# 5ButtonSwitch_ItsyBitsyM0_Rev1_1.net
KiCad netlist of a schematic drawn in EAGLE
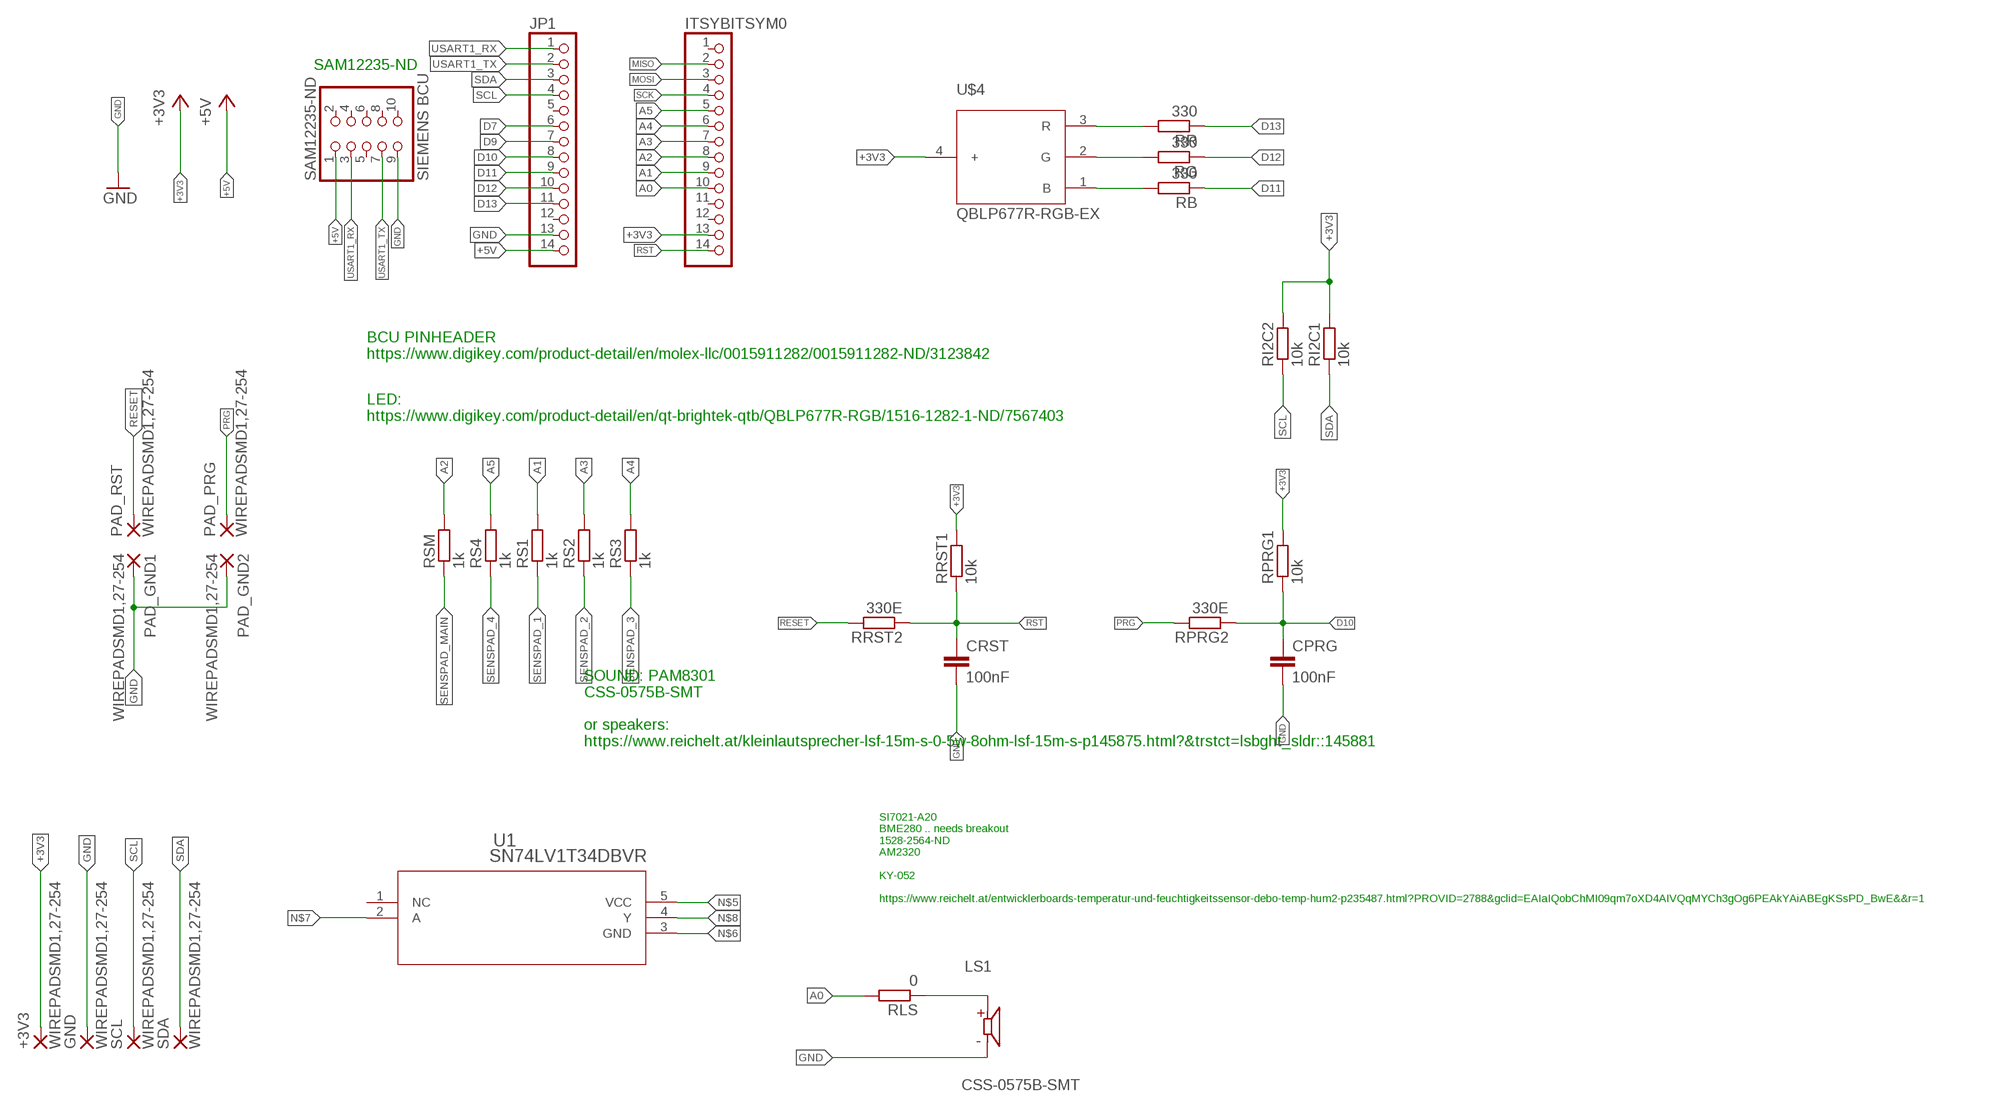
[diagram p0: schematic, sheet 1]

(export (version "E")
  (design (tool "Eeschema 10.0.6"))
  (components
    (comp (ref "+3V3")
      (value "WIREPADSMD1,27-254")
      (footprint "eagle-import:SMD1,27-2,54")
      (libsource (lib "eagle-import") (part "WIREPADSMD1,27-254"))
    )
    (comp (ref "CPRG")
      (value "100nF")
      (footprint "eagle-import:C1206")
      (libsource (lib "eagle-import") (part "C-EUC1206"))
    )
    (comp (ref "CRST")
      (value "100nF")
      (footprint "eagle-import:C1206")
      (libsource (lib "eagle-import") (part "C-EUC1206"))
    )
    (comp (ref "GND")
      (value "WIREPADSMD1,27-254")
      (footprint "eagle-import:SMD1,27-2,54")
      (libsource (lib "eagle-import") (part "WIREPADSMD1,27-254"))
    )
    (comp (ref "ITSYBITSYM0")
      (value "PINHD-1X141X14_SMT")
      (footprint "eagle-import:1X14_SMT")
      (libsource (lib "eagle-import") (part "PINHD-1X141X14_SMT"))
    )
    (comp (ref "JP1")
      (value "PINHD-1X141X14_SMT")
      (footprint "eagle-import:1X14_SMT")
      (libsource (lib "eagle-import") (part "PINHD-1X141X14_SMT"))
    )
    (comp (ref "LS1")
      (value "CSS-0575B-SMT")
      (footprint "eagle-import:CUI_CSS-0575B-SMT")
      (fields
        (field (name "DIGI-KEY_PART_NUMBER") "102-2202-1-ND")
        (field (name "MF") "CUI Inc.")
        (field (name "MP") "CSS-0575B-SMT-TR")
      )
      (libsource (lib "eagle-import") (part "CSS-0575B-SMT"))
    )
    (comp (ref "PAD_GND1")
      (value "WIREPADSMD1,27-254")
      (footprint "eagle-import:SMD1,27-2,54")
      (libsource (lib "eagle-import") (part "WIREPADSMD1,27-254"))
    )
    (comp (ref "PAD_GND2")
      (value "WIREPADSMD1,27-254")
      (footprint "eagle-import:SMD1,27-2,54")
      (libsource (lib "eagle-import") (part "WIREPADSMD1,27-254"))
    )
    (comp (ref "PAD_PRG")
      (value "WIREPADSMD1,27-254")
      (footprint "eagle-import:SMD1,27-2,54")
      (libsource (lib "eagle-import") (part "WIREPADSMD1,27-254"))
    )
    (comp (ref "PAD_RST")
      (value "WIREPADSMD1,27-254")
      (footprint "eagle-import:SMD1,27-2,54")
      (libsource (lib "eagle-import") (part "WIREPADSMD1,27-254"))
    )
    (comp (ref "RB")
      (value "330")
      (footprint "eagle-import:R1206")
      (libsource (lib "eagle-import") (part "R-EU_R1206"))
    )
    (comp (ref "RG")
      (value "330")
      (footprint "eagle-import:R1206")
      (libsource (lib "eagle-import") (part "R-EU_R1206"))
    )
    (comp (ref "RI2C1")
      (value "10k")
      (footprint "eagle-import:R1206")
      (libsource (lib "eagle-import") (part "R-EU_R1206"))
    )
    (comp (ref "RI2C2")
      (value "10k")
      (footprint "eagle-import:R1206")
      (libsource (lib "eagle-import") (part "R-EU_R1206"))
    )
    (comp (ref "RLS")
      (value "0")
      (footprint "eagle-import:R1206")
      (libsource (lib "eagle-import") (part "R-EU_R1206"))
    )
    (comp (ref "RPRG1")
      (value "10k")
      (footprint "eagle-import:R1206")
      (libsource (lib "eagle-import") (part "R-EU_R1206"))
    )
    (comp (ref "RPRG2")
      (value "330E")
      (footprint "eagle-import:R1206")
      (libsource (lib "eagle-import") (part "R-EU_R1206"))
    )
    (comp (ref "RR")
      (value "330")
      (footprint "eagle-import:R1206")
      (libsource (lib "eagle-import") (part "R-EU_R1206"))
    )
    (comp (ref "RRST1")
      (value "10k")
      (footprint "eagle-import:R1206")
      (libsource (lib "eagle-import") (part "R-EU_R1206"))
    )
    (comp (ref "RRST2")
      (value "330E")
      (footprint "eagle-import:R1206")
      (libsource (lib "eagle-import") (part "R-EU_R1206"))
    )
    (comp (ref "RS1")
      (value "1k")
      (footprint "eagle-import:R1206")
      (libsource (lib "eagle-import") (part "R-EU_R1206"))
    )
    (comp (ref "RS2")
      (value "1k")
      (footprint "eagle-import:R1206")
      (libsource (lib "eagle-import") (part "R-EU_R1206"))
    )
    (comp (ref "RS3")
      (value "1k")
      (footprint "eagle-import:R1206")
      (libsource (lib "eagle-import") (part "R-EU_R1206"))
    )
    (comp (ref "RS4")
      (value "1k")
      (footprint "eagle-import:R1206")
      (libsource (lib "eagle-import") (part "R-EU_R1206"))
    )
    (comp (ref "RSM")
      (value "1k")
      (footprint "eagle-import:R1206")
      (libsource (lib "eagle-import") (part "R-EU_R1206"))
    )
    (comp (ref "SAM12235-ND")
      (value "SIEMENS BCU")
      (footprint "eagle-import:2X05SMD")
      (libsource (lib "eagle-import") (part "PINHD-2X5_2.54-SMD"))
    )
    (comp (ref "SCL")
      (value "WIREPADSMD1,27-254")
      (footprint "eagle-import:SMD1,27-2,54")
      (libsource (lib "eagle-import") (part "WIREPADSMD1,27-254"))
    )
    (comp (ref "SDA")
      (value "WIREPADSMD1,27-254")
      (footprint "eagle-import:SMD1,27-2,54")
      (libsource (lib "eagle-import") (part "WIREPADSMD1,27-254"))
    )
    (comp (ref "U$4")
      (value "QBLP677R-RGB-EX")
      (footprint "eagle-import:PLCC4R_EX")
      (libsource (lib "eagle-import") (part "QBLP677R-RGB-EX"))
    )
    (comp (ref "U1")
      (value "SN74LV1T34DBVR")
      (footprint "eagle-import:DBV5")
      (libsource (lib "eagle-import") (part "SN74LV1T34DBVR"))
    )
  )
  (nets
    (net (code "1") (name "+3V3") (class "Default")
      (node (ref "+3V3") (pin "1") (pinfunction "P_1") (pintype "passive"))
      (node (ref "ITSYBITSYM0") (pin "13") (pinfunction "13_13") (pintype "passive"))
      (node (ref "RI2C1") (pin "2") (pinfunction "2_2") (pintype "passive"))
      (node (ref "RI2C2") (pin "2") (pinfunction "2_2") (pintype "passive"))
      (node (ref "RPRG1") (pin "2") (pinfunction "2_2") (pintype "passive"))
      (node (ref "RRST1") (pin "2") (pinfunction "2_2") (pintype "passive"))
      (node (ref "U$4") (pin "4") (pinfunction "+_4") (pintype "power_in"))
    )
    (net (code "2") (name "+5V") (class "Default")
      (node (ref "JP1") (pin "14") (pinfunction "14_14") (pintype "passive"))
      (node (ref "SAM12235-ND") (pin "1") (pinfunction "1_1") (pintype "passive"))
    )
    (net (code "3") (name "A0") (class "Default")
      (node (ref "ITSYBITSYM0") (pin "10") (pinfunction "10_10") (pintype "passive"))
      (node (ref "RLS") (pin "2") (pinfunction "2_2") (pintype "passive"))
    )
    (net (code "4") (name "A1") (class "Default")
      (node (ref "ITSYBITSYM0") (pin "9") (pinfunction "9_9") (pintype "passive"))
      (node (ref "RS1") (pin "2") (pinfunction "2_2") (pintype "passive"))
    )
    (net (code "5") (name "A2") (class "Default")
      (node (ref "ITSYBITSYM0") (pin "8") (pinfunction "8_8") (pintype "passive"))
      (node (ref "RSM") (pin "2") (pinfunction "2_2") (pintype "passive"))
    )
    (net (code "6") (name "A3") (class "Default")
      (node (ref "ITSYBITSYM0") (pin "7") (pinfunction "7_7") (pintype "passive"))
      (node (ref "RS2") (pin "2") (pinfunction "2_2") (pintype "passive"))
    )
    (net (code "7") (name "A4") (class "Default")
      (node (ref "ITSYBITSYM0") (pin "6") (pinfunction "6_6") (pintype "passive"))
      (node (ref "RS3") (pin "2") (pinfunction "2_2") (pintype "passive"))
    )
    (net (code "8") (name "A5") (class "Default")
      (node (ref "ITSYBITSYM0") (pin "5") (pinfunction "5_5") (pintype "passive"))
      (node (ref "RS4") (pin "2") (pinfunction "2_2") (pintype "passive"))
    )
    (net (code "9") (name "D7") (class "Default")
      (node (ref "JP1") (pin "6") (pinfunction "6_6") (pintype "passive"))
    )
    (net (code "10") (name "D9") (class "Default")
      (node (ref "JP1") (pin "7") (pinfunction "7_7") (pintype "passive"))
    )
    (net (code "11") (name "D10") (class "Default")
      (node (ref "CPRG") (pin "1") (pinfunction "1_1") (pintype "passive"))
      (node (ref "JP1") (pin "8") (pinfunction "8_8") (pintype "passive"))
      (node (ref "RPRG1") (pin "1") (pinfunction "1_1") (pintype "passive"))
      (node (ref "RPRG2") (pin "1") (pinfunction "1_1") (pintype "passive"))
    )
    (net (code "12") (name "D11") (class "Default")
      (node (ref "JP1") (pin "9") (pinfunction "9_9") (pintype "passive"))
      (node (ref "RB") (pin "1") (pinfunction "1_1") (pintype "passive"))
    )
    (net (code "13") (name "D12") (class "Default")
      (node (ref "JP1") (pin "10") (pinfunction "10_10") (pintype "passive"))
      (node (ref "RG") (pin "1") (pinfunction "1_1") (pintype "passive"))
    )
    (net (code "14") (name "D13") (class "Default")
      (node (ref "JP1") (pin "11") (pinfunction "11_11") (pintype "passive"))
      (node (ref "RR") (pin "1") (pinfunction "1_1") (pintype "passive"))
    )
    (net (code "15") (name "GND") (class "Default")
      (node (ref "CPRG") (pin "2") (pinfunction "2_2") (pintype "passive"))
      (node (ref "CRST") (pin "2") (pinfunction "2_2") (pintype "passive"))
      (node (ref "GND") (pin "1") (pinfunction "P_1") (pintype "passive"))
      (node (ref "JP1") (pin "13") (pinfunction "13_13") (pintype "passive"))
      (node (ref "LS1") (pin "2") (pinfunction "N_2") (pintype "passive"))
      (node (ref "PAD_GND1") (pin "1") (pinfunction "P_1") (pintype "passive"))
      (node (ref "PAD_GND2") (pin "1") (pinfunction "P_1") (pintype "passive"))
      (node (ref "SAM12235-ND") (pin "9") (pinfunction "9_9") (pintype "passive"))
    )
    (net (code "16") (name "MISO") (class "Default")
      (node (ref "ITSYBITSYM0") (pin "2") (pinfunction "2_2") (pintype "passive"))
    )
    (net (code "17") (name "MOSI") (class "Default")
      (node (ref "ITSYBITSYM0") (pin "3") (pinfunction "3_3") (pintype "passive"))
    )
    (net (code "18") (name "N$5") (class "Default")
      (node (ref "U1") (pin "5") (pinfunction "VCC_5") (pintype "power_in"))
    )
    (net (code "19") (name "N$6") (class "Default")
      (node (ref "U1") (pin "3") (pinfunction "GND_3") (pintype "power_in"))
    )
    (net (code "20") (name "N$7") (class "Default")
      (node (ref "U1") (pin "2") (pinfunction "A_2") (pintype "input"))
    )
    (net (code "21") (name "N$8") (class "Default")
      (node (ref "U1") (pin "4") (pinfunction "Y_4") (pintype "output"))
    )
    (net (code "22") (name "Net-(LS1-P)") (class "Default")
      (node (ref "LS1") (pin "1") (pinfunction "P_1") (pintype "passive"))
      (node (ref "RLS") (pin "1") (pinfunction "1_1") (pintype "passive"))
    )
    (net (code "23") (name "Net-(U$4-B)") (class "Default")
      (node (ref "RB") (pin "2") (pinfunction "2_2") (pintype "passive"))
      (node (ref "U$4") (pin "1") (pinfunction "B_1") (pintype "output"))
    )
    (net (code "24") (name "Net-(U$4-G)") (class "Default")
      (node (ref "RG") (pin "2") (pinfunction "2_2") (pintype "passive"))
      (node (ref "U$4") (pin "2") (pinfunction "G_2") (pintype "output"))
    )
    (net (code "25") (name "Net-(U$4-R)") (class "Default")
      (node (ref "RR") (pin "2") (pinfunction "2_2") (pintype "passive"))
      (node (ref "U$4") (pin "3") (pinfunction "R_3") (pintype "output"))
    )
    (net (code "26") (name "PRG") (class "Default")
      (node (ref "PAD_PRG") (pin "1") (pinfunction "P_1") (pintype "passive"))
      (node (ref "RPRG2") (pin "2") (pinfunction "2_2") (pintype "passive"))
    )
    (net (code "27") (name "RESET") (class "Default")
      (node (ref "PAD_RST") (pin "1") (pinfunction "P_1") (pintype "passive"))
      (node (ref "RRST2") (pin "2") (pinfunction "2_2") (pintype "passive"))
    )
    (net (code "28") (name "RST") (class "Default")
      (node (ref "CRST") (pin "1") (pinfunction "1_1") (pintype "passive"))
      (node (ref "ITSYBITSYM0") (pin "14") (pinfunction "14_14") (pintype "passive"))
      (node (ref "RRST1") (pin "1") (pinfunction "1_1") (pintype "passive"))
      (node (ref "RRST2") (pin "1") (pinfunction "1_1") (pintype "passive"))
    )
    (net (code "29") (name "SCK") (class "Default")
      (node (ref "ITSYBITSYM0") (pin "4") (pinfunction "4_4") (pintype "passive"))
    )
    (net (code "30") (name "SCL") (class "Default")
      (node (ref "JP1") (pin "4") (pinfunction "4_4") (pintype "passive"))
      (node (ref "RI2C2") (pin "1") (pinfunction "1_1") (pintype "passive"))
      (node (ref "SCL") (pin "1") (pinfunction "P_1") (pintype "passive"))
    )
    (net (code "31") (name "SDA") (class "Default")
      (node (ref "JP1") (pin "3") (pinfunction "3_3") (pintype "passive"))
      (node (ref "RI2C1") (pin "1") (pinfunction "1_1") (pintype "passive"))
      (node (ref "SDA") (pin "1") (pinfunction "P_1") (pintype "passive"))
    )
    (net (code "32") (name "SENSPAD_1") (class "Default")
      (node (ref "RS1") (pin "1") (pinfunction "1_1") (pintype "passive"))
    )
    (net (code "33") (name "SENSPAD_2") (class "Default")
      (node (ref "RS2") (pin "1") (pinfunction "1_1") (pintype "passive"))
    )
    (net (code "34") (name "SENSPAD_3") (class "Default")
      (node (ref "RS3") (pin "1") (pinfunction "1_1") (pintype "passive"))
    )
    (net (code "35") (name "SENSPAD_4") (class "Default")
      (node (ref "RS4") (pin "1") (pinfunction "1_1") (pintype "passive"))
    )
    (net (code "36") (name "SENSPAD_MAIN") (class "Default")
      (node (ref "RSM") (pin "1") (pinfunction "1_1") (pintype "passive"))
    )
    (net (code "37") (name "USART1_RX") (class "Default")
      (node (ref "JP1") (pin "1") (pinfunction "1_1") (pintype "passive"))
      (node (ref "SAM12235-ND") (pin "3") (pinfunction "3_3") (pintype "passive"))
    )
    (net (code "38") (name "USART1_TX") (class "Default")
      (node (ref "JP1") (pin "2") (pinfunction "2_2") (pintype "passive"))
      (node (ref "SAM12235-ND") (pin "7") (pinfunction "7_7") (pintype "passive"))
    )
    (net (code "39") (name "unconnected-(ITSYBITSYM0-Pad1)") (class "Default")
      (node (ref "ITSYBITSYM0") (pin "1") (pinfunction "1_1") (pintype "passive"))
    )
    (net (code "40") (name "unconnected-(ITSYBITSYM0-Pad11)") (class "Default")
      (node (ref "ITSYBITSYM0") (pin "11") (pinfunction "11_11") (pintype "passive"))
    )
    (net (code "41") (name "unconnected-(ITSYBITSYM0-Pad12)") (class "Default")
      (node (ref "ITSYBITSYM0") (pin "12") (pinfunction "12_12") (pintype "passive"))
    )
    (net (code "42") (name "unconnected-(JP1-Pad5)") (class "Default")
      (node (ref "JP1") (pin "5") (pinfunction "5_5") (pintype "passive"))
    )
    (net (code "43") (name "unconnected-(JP1-Pad12)") (class "Default")
      (node (ref "JP1") (pin "12") (pinfunction "12_12") (pintype "passive"))
    )
    (net (code "44") (name "unconnected-(SAM12235-ND-Pad2)") (class "Default")
      (node (ref "SAM12235-ND") (pin "2") (pinfunction "2_2") (pintype "passive"))
    )
    (net (code "45") (name "unconnected-(SAM12235-ND-Pad4)") (class "Default")
      (node (ref "SAM12235-ND") (pin "4") (pinfunction "4_4") (pintype "passive"))
    )
    (net (code "46") (name "unconnected-(SAM12235-ND-Pad5)") (class "Default")
      (node (ref "SAM12235-ND") (pin "5") (pinfunction "5_5") (pintype "passive"))
    )
    (net (code "47") (name "unconnected-(SAM12235-ND-Pad6)") (class "Default")
      (node (ref "SAM12235-ND") (pin "6") (pinfunction "6_6") (pintype "passive"))
    )
    (net (code "48") (name "unconnected-(SAM12235-ND-Pad8)") (class "Default")
      (node (ref "SAM12235-ND") (pin "8") (pinfunction "8_8") (pintype "passive"))
    )
    (net (code "49") (name "unconnected-(SAM12235-ND-Pad10)") (class "Default")
      (node (ref "SAM12235-ND") (pin "10") (pinfunction "10_10") (pintype "passive"))
    )
    (net (code "50") (name "unconnected-(U1-NC-Pad1)") (class "Default")
      (node (ref "U1") (pin "1") (pinfunction "NC_1") (pintype "no_connect"))
    )
  )
)
